# Adafruit_Feather_STM32F405_Express.net
KiCad netlist of a schematic drawn in EAGLE
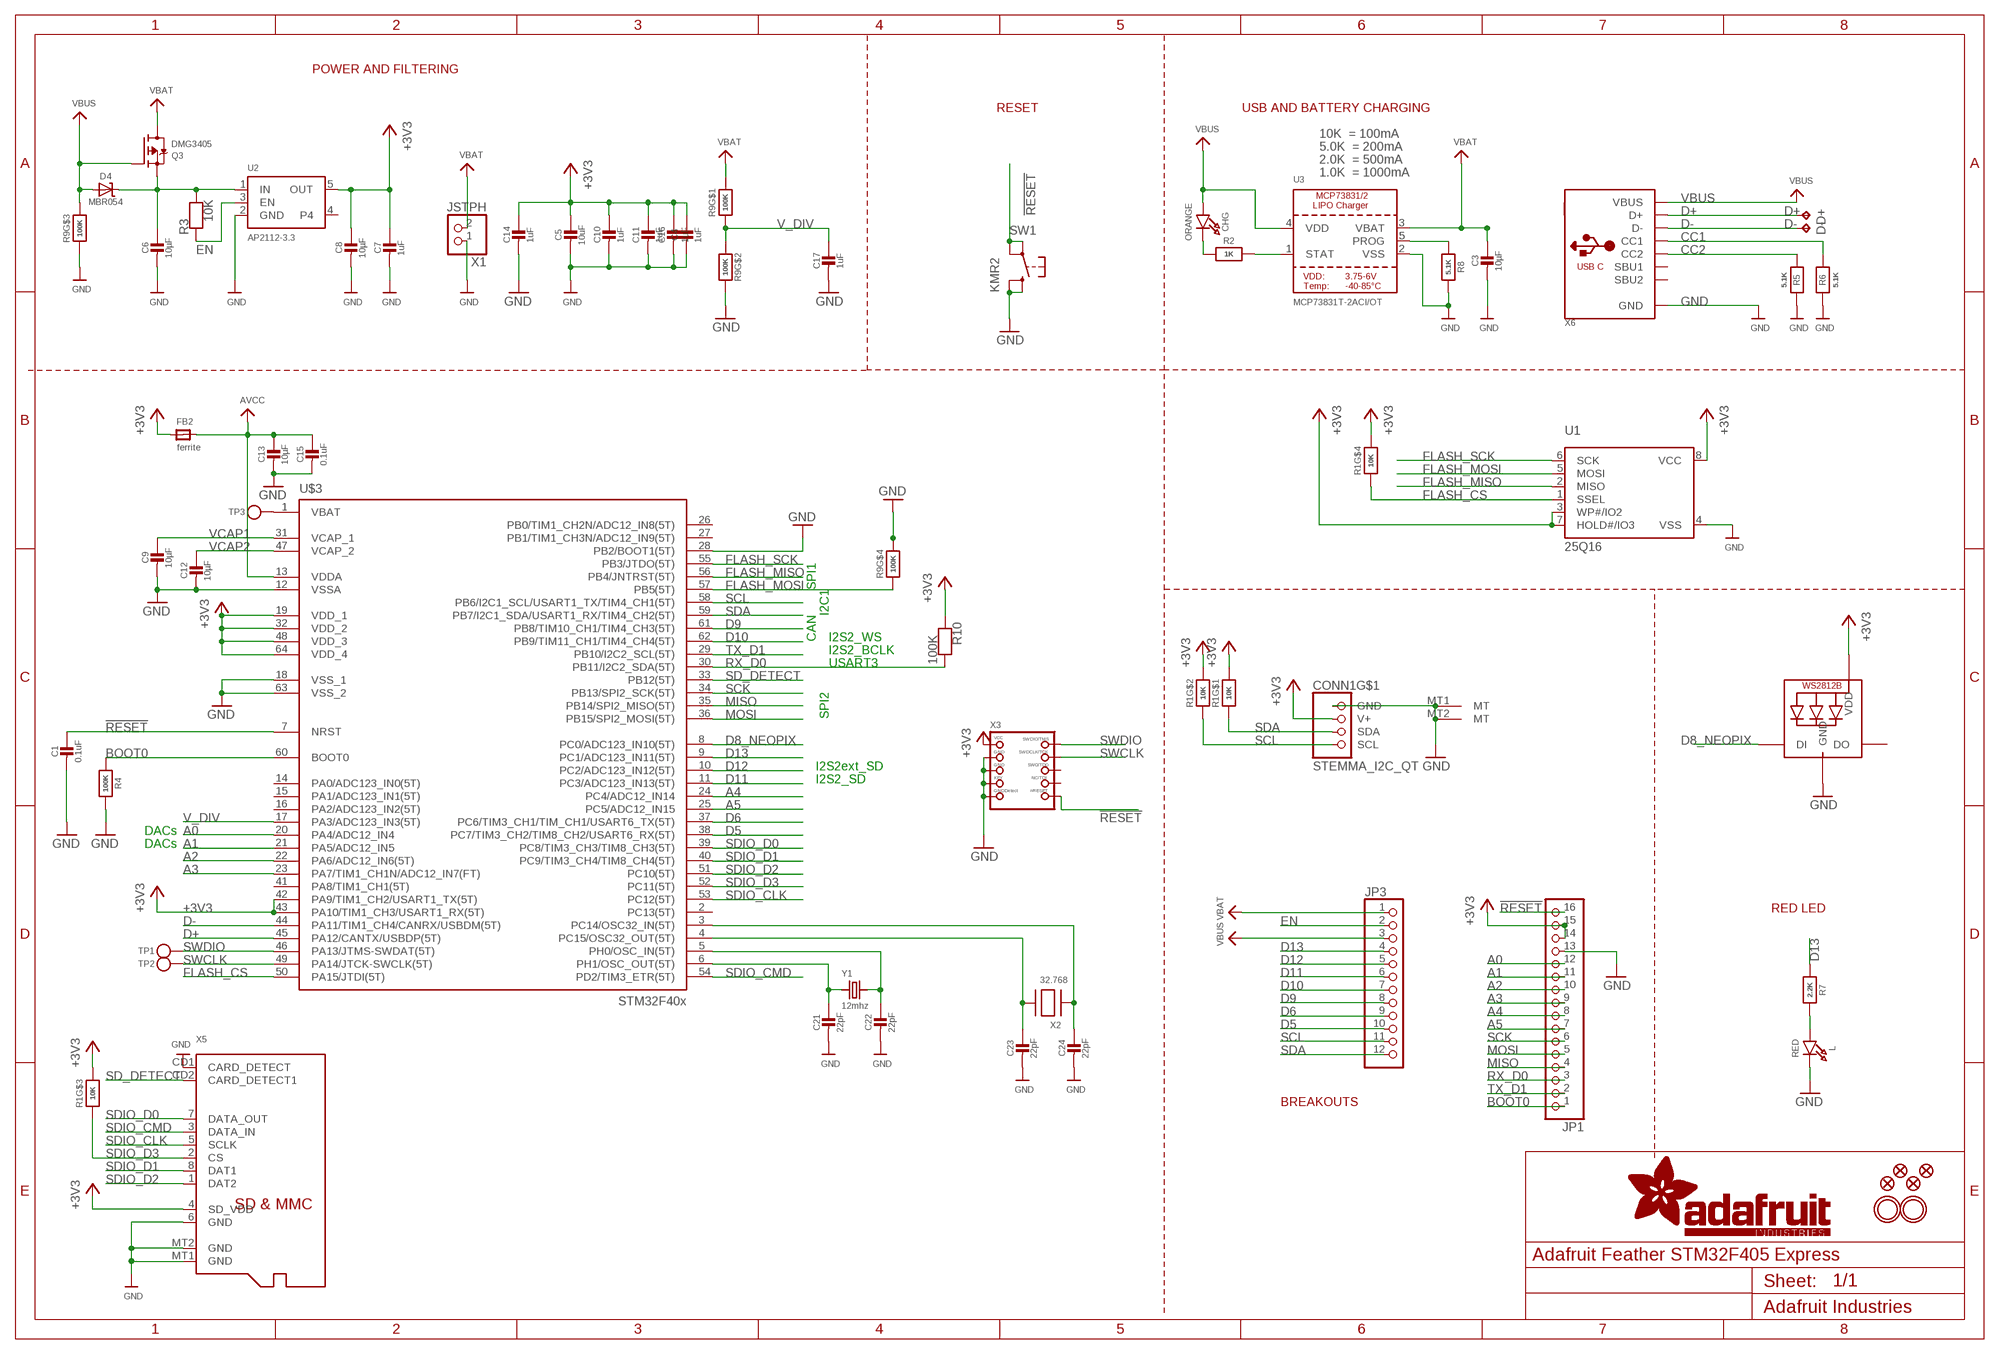
[diagram p0: schematic, sheet 1]

(export (version "E")
  (design (tool "Eeschema 10.0.6"))
  (components
    (comp (ref "C1")
      (value "0.1uF")
      (footprint "eagle-import:0603-NO")
      (libsource (lib "eagle-import") (part "CAP_CERAMIC0603_NO"))
    )
    (comp (ref "C2")
      (value "22pF")
      (footprint "eagle-import:RESPACK_4X0603")
      (libsource (lib "eagle-import") (part "CAP_4PACK1206"))
    )
    (comp (ref "C3")
      (value "10µF")
      (footprint "eagle-import:0805-NO")
      (libsource (lib "eagle-import") (part "CAP_CERAMIC0805-NOOUTLINE"))
    )
    (comp (ref "C4")
      (value "1uF")
      (footprint "eagle-import:0603-NO")
      (libsource (lib "eagle-import") (part "CAP_CERAMIC0603_NO"))
    )
    (comp (ref "C5")
      (value "10uF")
      (footprint "eagle-import:0805-NO")
      (libsource (lib "eagle-import") (part "CAP_CERAMIC0805-NOOUTLINE"))
    )
    (comp (ref "C6")
      (value "10µF")
      (footprint "eagle-import:0805-NO")
      (libsource (lib "eagle-import") (part "CAP_CERAMIC0805-NOOUTLINE"))
    )
    (comp (ref "C7")
      (value "1uF")
      (footprint "eagle-import:0603-NO")
      (libsource (lib "eagle-import") (part "CAP_CERAMIC0603_NO"))
    )
    (comp (ref "C8")
      (value "10µF")
      (footprint "eagle-import:0805-NO")
      (fields (field (name "REV") "B"))
      (libsource (lib "eagle-import") (part "CAP_CERAMIC0805-NOOUTLINE"))
    )
    (comp (ref "C9")
      (value "10µF")
      (footprint "eagle-import:0805-NO")
      (libsource (lib "eagle-import") (part "CAP_CERAMIC0805-NOOUTLINE"))
    )
    (comp (ref "C10")
      (value "1uF")
      (footprint "eagle-import:0603-NO")
      (libsource (lib "eagle-import") (part "CAP_CERAMIC0603_NO"))
    )
    (comp (ref "C11")
      (value "1uF")
      (footprint "eagle-import:0603-NO")
      (libsource (lib "eagle-import") (part "CAP_CERAMIC0603_NO"))
    )
    (comp (ref "C12")
      (value "10µF")
      (footprint "eagle-import:0805-NO")
      (libsource (lib "eagle-import") (part "CAP_CERAMIC0805-NOOUTLINE"))
    )
    (comp (ref "C13")
      (value "10µF")
      (footprint "eagle-import:0805-NO")
      (libsource (lib "eagle-import") (part "CAP_CERAMIC0805-NOOUTLINE"))
    )
    (comp (ref "C14")
      (value "1uF")
      (footprint "eagle-import:0603-NO")
      (libsource (lib "eagle-import") (part "CAP_CERAMIC0603_NO"))
    )
    (comp (ref "C15")
      (value "0.1uF")
      (footprint "eagle-import:0603-NO")
      (libsource (lib "eagle-import") (part "CAP_CERAMIC0603_NO"))
    )
    (comp (ref "C16")
      (value "1uF")
      (footprint "eagle-import:0603-NO")
      (libsource (lib "eagle-import") (part "CAP_CERAMIC0603_NO"))
    )
    (comp (ref "C17")
      (value "1uF")
      (footprint "eagle-import:0603-NO")
      (libsource (lib "eagle-import") (part "CAP_CERAMIC0603_NO"))
    )
    (comp (ref "CHG")
      (value "ORANGE")
      (footprint "eagle-import:CHIPLED_0805_NOOUTLINE")
      (libsource (lib "eagle-import") (part "LED0805_NOOUTLINE"))
    )
    (comp (ref "CONN1")
      (value "STEMMA_I2C_QT")
      (footprint "eagle-import:JST_SH4")
      (libsource (lib "eagle-import") (part "STEMMA_I2C_QT"))
    )
    (comp (ref "D+")
      (value "TPB1,27")
      (footprint "eagle-import:B1,27")
      (libsource (lib "eagle-import") (part "TPB1,27"))
    )
    (comp (ref "D-")
      (value "TPB1,27")
      (footprint "eagle-import:B1,27")
      (libsource (lib "eagle-import") (part "TPB1,27"))
    )
    (comp (ref "D4")
      (value "MBR054")
      (footprint "eagle-import:SOD-123")
      (libsource (lib "eagle-import") (part "DIODE-SCHOTTKYSOD-123"))
    )
    (comp (ref "FB2")
      (value "ferrite")
      (footprint "eagle-import:0805-NO")
      (libsource (lib "eagle-import") (part "FERRITE-0805NO"))
    )
    (comp (ref "JP1")
      (value "HEADER-1X16ROUND")
      (footprint "eagle-import:1X16_ROUND")
      (libsource (lib "eagle-import") (part "HEADER-1X16ROUND"))
    )
    (comp (ref "JP3")
      (value "HEADER-1X12")
      (footprint "eagle-import:1X12_ROUND")
      (libsource (lib "eagle-import") (part "HEADER-1X12"))
    )
    (comp (ref "L")
      (value "RED")
      (footprint "eagle-import:CHIPLED_0805_NOOUTLINE")
      (libsource (lib "eagle-import") (part "LED0805_NOOUTLINE"))
    )
    (comp (ref "LED1")
      (value "WS2812B3535")
      (footprint "eagle-import:LED3535")
      (libsource (lib "eagle-import") (part "WS2812B3535"))
    )
    (comp (ref "Q3")
      (value "DMG3405")
      (footprint "eagle-import:SOT23-R")
      (libsource (lib "eagle-import") (part "MOSFET-P"))
    )
    (comp (ref "R1")
      (value "10K")
      (footprint "eagle-import:RESPACK_4X0603_NO")
      (libsource (lib "eagle-import") (part "RESISTOR_4PACK_NO"))
    )
    (comp (ref "R2")
      (value "1K")
      (footprint "eagle-import:0603-NO")
      (libsource (lib "eagle-import") (part "RESISTOR_0603_NOOUT"))
    )
    (comp (ref "R3")
      (value "10K")
      (footprint "eagle-import:0603-NO")
      (libsource (lib "eagle-import") (part "RESISTOR_0603_NOOUT"))
    )
    (comp (ref "R4")
      (value "100K")
      (footprint "eagle-import:0603-NO")
      (libsource (lib "eagle-import") (part "RESISTOR_0603_NOOUT"))
    )
    (comp (ref "R5")
      (value "5.1K")
      (footprint "eagle-import:0603-NO")
      (libsource (lib "eagle-import") (part "RESISTOR_0603_NOOUT"))
    )
    (comp (ref "R6")
      (value "5.1K")
      (footprint "eagle-import:0603-NO")
      (libsource (lib "eagle-import") (part "RESISTOR_0603_NOOUT"))
    )
    (comp (ref "R7")
      (value "2.2K")
      (footprint "eagle-import:0603-NO")
      (libsource (lib "eagle-import") (part "RESISTOR_0603_NOOUT"))
    )
    (comp (ref "R8")
      (value "5.1K")
      (footprint "eagle-import:0603-NO")
      (libsource (lib "eagle-import") (part "RESISTOR_0603_NOOUT"))
    )
    (comp (ref "R9")
      (value "100K")
      (footprint "eagle-import:RESPACK_4X0603_NO")
      (libsource (lib "eagle-import") (part "RESISTOR_4PACK_NO"))
    )
    (comp (ref "R10")
      (value "100K")
      (footprint "eagle-import:0603-NO")
      (libsource (lib "eagle-import") (part "RESISTOR_0603_NOOUT"))
    )
    (comp (ref "SW1")
      (value "KMR2")
      (footprint "eagle-import:BTN_KMR2_4.6X2.8")
      (libsource (lib "eagle-import") (part "SWITCH_TACT_SMT4.6X2.8"))
    )
    (comp (ref "TP1")
      (value "TESTPOINTROUND1.5MM")
      (footprint "eagle-import:TESTPOINT_ROUND_1.5MM")
      (libsource (lib "eagle-import") (part "TESTPOINTROUND1.5MM"))
    )
    (comp (ref "TP2")
      (value "TESTPOINTROUND1.5MM")
      (footprint "eagle-import:TESTPOINT_ROUND_1.5MM")
      (libsource (lib "eagle-import") (part "TESTPOINTROUND1.5MM"))
    )
    (comp (ref "TP3")
      (value "TESTPOINTROUND1.5MM")
      (footprint "eagle-import:TESTPOINT_ROUND_1.5MM")
      (libsource (lib "eagle-import") (part "TESTPOINTROUND1.5MM"))
    )
    (comp (ref "U$3")
      (value "STM32F405R")
      (footprint "eagle-import:TQFP64")
      (libsource (lib "eagle-import") (part "STM32F405R"))
    )
    (comp (ref "U$5")
      (value "FIDUCIAL_1MM")
      (footprint "eagle-import:FIDUCIAL_1MM")
      (libsource (lib "eagle-import") (part "FIDUCIAL_1MM"))
    )
    (comp (ref "U$31")
      (value "MOUNTINGHOLE2.5")
      (footprint "eagle-import:MOUNTINGHOLE_2.5_PLATED")
      (libsource (lib "eagle-import") (part "MOUNTINGHOLE2.5"))
    )
    (comp (ref "U$32")
      (value "MOUNTINGHOLE2.5")
      (footprint "eagle-import:MOUNTINGHOLE_2.5_PLATED")
      (libsource (lib "eagle-import") (part "MOUNTINGHOLE2.5"))
    )
    (comp (ref "U$34")
      (value "FIDUCIAL_1MM")
      (footprint "eagle-import:FIDUCIAL_1MM")
      (libsource (lib "eagle-import") (part "FIDUCIAL_1MM"))
    )
    (comp (ref "U$35")
      (value "FIDUCIAL_1MM")
      (footprint "eagle-import:FIDUCIAL_1MM")
      (libsource (lib "eagle-import") (part "FIDUCIAL_1MM"))
    )
    (comp (ref "U$37")
      (value "FIDUCIAL_1MM")
      (footprint "eagle-import:FIDUCIAL_1MM")
      (libsource (lib "eagle-import") (part "FIDUCIAL_1MM"))
    )
    (comp (ref "U1")
      (value "25Q16")
      (footprint "eagle-import:SOIC8_150MIL")
      (libsource (lib "eagle-import") (part "SPIFLASH_8PIN"))
    )
    (comp (ref "U2")
      (value "AP2112-3.3")
      (footprint "eagle-import:SOT23-5")
      (libsource (lib "eagle-import") (part "VREG_SOT23-5"))
    )
    (comp (ref "U3")
      (value "MCP73831T-2ACI/OT")
      (footprint "eagle-import:SOT23-5")
      (libsource (lib "eagle-import") (part "MCP73831/2"))
    )
    (comp (ref "X1")
      (value "JSTPH")
      (footprint "eagle-import:JSTPH2")
      (libsource (lib "eagle-import") (part "CON_JST_PH_2PIN"))
    )
    (comp (ref "X2")
      (value "32.768")
      (footprint "eagle-import:XTAL3215")
      (libsource (lib "eagle-import") (part "XTAL-3.2X1.5"))
    )
    (comp (ref "X3")
      (value "JTAG-CORTEX")
      (footprint "eagle-import:2X05_1.27MM_SMT")
      (libsource (lib "eagle-import") (part "JTAG-CORTEX"))
    )
    (comp (ref "X5")
      (value "MICROSD")
      (footprint "eagle-import:MICROSD")
      (libsource (lib "eagle-import") (part "MICROSD"))
    )
    (comp (ref "X6")
      (value "USB_C")
      (footprint "eagle-import:USB_C_CUSB31-CFM2AX-01-X")
      (libsource (lib "eagle-import") (part "USB_C"))
    )
    (comp (ref "Y1")
      (value "12mhz")
      (footprint "eagle-import:CRYSTAL_2.5X2")
      (libsource (lib "eagle-import") (part "CRYSTAL2.5X2.0"))
    )
  )
  (nets
    (net (code "1") (name "+3V3") (class "Default")
      (node (ref "C10") (pin "1") (pinfunction "1_1") (pintype "passive"))
      (node (ref "C11") (pin "1") (pinfunction "1_1") (pintype "passive"))
      (node (ref "C14") (pin "1") (pinfunction "1_1") (pintype "passive"))
      (node (ref "C16") (pin "1") (pinfunction "1_1") (pintype "passive"))
      (node (ref "C4") (pin "1") (pinfunction "1_1") (pintype "passive"))
      (node (ref "C5") (pin "1") (pinfunction "1_1") (pintype "passive"))
      (node (ref "C7") (pin "1") (pinfunction "1_1") (pintype "passive"))
      (node (ref "C8") (pin "1") (pinfunction "1_1") (pintype "passive"))
      (node (ref "CONN1") (pin "2") (pinfunction "V+_2") (pintype "passive"))
      (node (ref "FB2") (pin "1") (pinfunction "P$1_1") (pintype "passive"))
      (node (ref "JP1") (pin "14") (pinfunction "14_14") (pintype "passive"))
      (node (ref "JP1") (pin "15") (pinfunction "15_15") (pintype "passive"))
      (node (ref "LED1") (pin "2") (pinfunction "VDD_2") (pintype "power_in"))
      (node (ref "R1") (pin "5") (pinfunction "2_5") (pintype "passive"))
      (node (ref "R1") (pin "6") (pinfunction "2_6") (pintype "passive"))
      (node (ref "R1") (pin "7") (pinfunction "2_7") (pintype "passive"))
      (node (ref "R1") (pin "8") (pinfunction "2_8") (pintype "passive"))
      (node (ref "R10") (pin "1") (pinfunction "1_1") (pintype "passive"))
      (node (ref "U$3") (pin "19") (pinfunction "VDD_1_19") (pintype "bidirectional"))
      (node (ref "U$3") (pin "32") (pinfunction "VDD_2_32") (pintype "bidirectional"))
      (node (ref "U$3") (pin "42") (pinfunction "PA9/TIM1_CH2/USART1_TX(5T)_42") (pintype "bidirectional"))
      (node (ref "U$3") (pin "43") (pinfunction "PA10/TIM1_CH3/USART1_RX(5T)_43") (pintype "bidirectional"))
      (node (ref "U$3") (pin "48") (pinfunction "VDD_3_48") (pintype "bidirectional"))
      (node (ref "U$3") (pin "64") (pinfunction "VDD_4_64") (pintype "bidirectional"))
      (node (ref "U1") (pin "3") (pinfunction "WP#/IO2_3") (pintype "bidirectional"))
      (node (ref "U1") (pin "7") (pinfunction "HOLD#/IO3_7") (pintype "bidirectional"))
      (node (ref "U1") (pin "8") (pinfunction "VCC_8") (pintype "bidirectional"))
      (node (ref "U2") (pin "5") (pinfunction "OUT_5") (pintype "power_in"))
      (node (ref "X3") (pin "1") (pinfunction "VCC_1") (pintype "power_in"))
      (node (ref "X5") (pin "4") (pinfunction "SD_VDD_4") (pintype "power_in"))
    )
    (net (code "2") (name "/A0") (class "Default")
      (node (ref "JP1") (pin "12") (pinfunction "12_12") (pintype "passive"))
      (node (ref "U$3") (pin "20") (pinfunction "PA4/ADC12_IN4_20") (pintype "bidirectional"))
    )
    (net (code "3") (name "/A1") (class "Default")
      (node (ref "JP1") (pin "11") (pinfunction "11_11") (pintype "passive"))
      (node (ref "U$3") (pin "21") (pinfunction "PA5/ADC12_IN5_21") (pintype "bidirectional"))
    )
    (net (code "4") (name "/A2") (class "Default")
      (node (ref "JP1") (pin "10") (pinfunction "10_10") (pintype "passive"))
      (node (ref "U$3") (pin "22") (pinfunction "PA6/ADC12_IN6(5T)_22") (pintype "bidirectional"))
    )
    (net (code "5") (name "/A3") (class "Default")
      (node (ref "JP1") (pin "9") (pinfunction "9_9") (pintype "passive"))
      (node (ref "U$3") (pin "23") (pinfunction "PA7/TIM1_CH1N/ADC12_IN7(FT)_23") (pintype "bidirectional"))
    )
    (net (code "6") (name "/A4") (class "Default")
      (node (ref "JP1") (pin "8") (pinfunction "8_8") (pintype "passive"))
      (node (ref "U$3") (pin "24") (pinfunction "PC4/ADC12_IN14_24") (pintype "bidirectional"))
    )
    (net (code "7") (name "/A5") (class "Default")
      (node (ref "JP1") (pin "7") (pinfunction "7_7") (pintype "passive"))
      (node (ref "U$3") (pin "25") (pinfunction "PC5/ADC12_IN15_25") (pintype "bidirectional"))
    )
    (net (code "8") (name "/BOOT0") (class "Default")
      (node (ref "JP1") (pin "1") (pinfunction "1_1") (pintype "passive"))
      (node (ref "R4") (pin "1") (pinfunction "1_1") (pintype "passive"))
      (node (ref "U$3") (pin "60") (pinfunction "BOOT0_60") (pintype "bidirectional"))
    )
    (net (code "9") (name "/CC1") (class "Default")
      (node (ref "R6") (pin "2") (pinfunction "2_2") (pintype "passive"))
      (node (ref "X6") (pin "A5") (pinfunction "CC1_A5") (pintype "bidirectional"))
    )
    (net (code "10") (name "/CC2") (class "Default")
      (node (ref "R5") (pin "2") (pinfunction "2_2") (pintype "passive"))
      (node (ref "X6") (pin "B5") (pinfunction "CC2_B5") (pintype "bidirectional"))
    )
    (net (code "11") (name "/D+") (class "Default")
      (node (ref "D+") (pin "TP") (pinfunction "TP_TP") (pintype "input"))
      (node (ref "U$3") (pin "45") (pinfunction "PA12/CANTX/USBDP(5T)_45") (pintype "bidirectional"))
      (node (ref "X6") (pin "A6") (pinfunction "D+_A6") (pintype "bidirectional"))
      (node (ref "X6") (pin "B6") (pinfunction "D+_B6") (pintype "bidirectional"))
    )
    (net (code "12") (name "/D-") (class "Default")
      (node (ref "D-") (pin "TP") (pinfunction "TP_TP") (pintype "input"))
      (node (ref "U$3") (pin "44") (pinfunction "PA11/TIM1_CH4/CANRX/USBDM(5T)_44") (pintype "bidirectional"))
      (node (ref "X6") (pin "A7") (pinfunction "D-_A7") (pintype "bidirectional"))
      (node (ref "X6") (pin "B7") (pinfunction "D-_B7") (pintype "bidirectional"))
    )
    (net (code "13") (name "/D5") (class "Default")
      (node (ref "JP3") (pin "10") (pinfunction "10_10") (pintype "passive"))
      (node (ref "U$3") (pin "38") (pinfunction "PC7/TIM3_CH2/TIM8_CH2/USART6_RX(5T)_38") (pintype "bidirectional"))
    )
    (net (code "14") (name "/D6") (class "Default")
      (node (ref "JP3") (pin "9") (pinfunction "9_9") (pintype "passive"))
      (node (ref "U$3") (pin "37") (pinfunction "PC6/TIM3_CH1/TIM_CH1/USART6_TX(5T)_37") (pintype "bidirectional"))
    )
    (net (code "15") (name "/D8_NEOPIX") (class "Default")
      (node (ref "LED1") (pin "1") (pinfunction "DI_1") (pintype "input"))
      (node (ref "U$3") (pin "8") (pinfunction "PC0/ADC123_IN10(5T)_8") (pintype "bidirectional"))
    )
    (net (code "16") (name "/D9") (class "Default")
      (node (ref "JP3") (pin "8") (pinfunction "8_8") (pintype "passive"))
      (node (ref "U$3") (pin "61") (pinfunction "PB8/TIM10_CH1/TIM4_CH3(5T)_61") (pintype "bidirectional"))
    )
    (net (code "17") (name "/D10") (class "Default")
      (node (ref "JP3") (pin "7") (pinfunction "7_7") (pintype "passive"))
      (node (ref "U$3") (pin "62") (pinfunction "PB9/TIM11_CH1/TIM4_CH4(5T)_62") (pintype "bidirectional"))
    )
    (net (code "18") (name "/D11") (class "Default")
      (node (ref "JP3") (pin "6") (pinfunction "6_6") (pintype "passive"))
      (node (ref "U$3") (pin "11") (pinfunction "PC3/ADC123_IN13(5T)_11") (pintype "bidirectional"))
    )
    (net (code "19") (name "/D12") (class "Default")
      (node (ref "JP3") (pin "5") (pinfunction "5_5") (pintype "passive"))
      (node (ref "U$3") (pin "10") (pinfunction "PC2/ADC123_IN12(5T)_10") (pintype "bidirectional"))
    )
    (net (code "20") (name "/D13") (class "Default")
      (node (ref "JP3") (pin "4") (pinfunction "4_4") (pintype "passive"))
      (node (ref "R7") (pin "1") (pinfunction "1_1") (pintype "passive"))
      (node (ref "U$3") (pin "9") (pinfunction "PC1/ADC123_IN11(5T)_9") (pintype "bidirectional"))
    )
    (net (code "21") (name "/EN") (class "Default")
      (node (ref "JP3") (pin "2") (pinfunction "2_2") (pintype "passive"))
      (node (ref "R3") (pin "1") (pinfunction "1_1") (pintype "passive"))
      (node (ref "U2") (pin "3") (pinfunction "EN_3") (pintype "input"))
    )
    (net (code "22") (name "/FLASH_CS") (class "Default")
      (node (ref "R1") (pin "4") (pinfunction "1_4") (pintype "passive"))
      (node (ref "U$3") (pin "50") (pinfunction "PA15/JTDI(5T)_50") (pintype "bidirectional"))
      (node (ref "U1") (pin "1") (pinfunction "SSEL_1") (pintype "bidirectional"))
    )
    (net (code "23") (name "/FLASH_MISO") (class "Default")
      (node (ref "U$3") (pin "56") (pinfunction "PB4/JNTRST(5T)_56") (pintype "bidirectional"))
      (node (ref "U1") (pin "2") (pinfunction "MISO_2") (pintype "bidirectional"))
    )
    (net (code "24") (name "/FLASH_MOSI") (class "Default")
      (node (ref "R9") (pin "4") (pinfunction "1_4") (pintype "passive"))
      (node (ref "U$3") (pin "57") (pinfunction "PB5(5T)_57") (pintype "bidirectional"))
      (node (ref "U1") (pin "5") (pinfunction "MOSI_5") (pintype "bidirectional"))
    )
    (net (code "25") (name "/FLASH_SCK") (class "Default")
      (node (ref "U$3") (pin "55") (pinfunction "PB3/JTDO(5T)_55") (pintype "bidirectional"))
      (node (ref "U1") (pin "6") (pinfunction "SCK_6") (pintype "bidirectional"))
    )
    (net (code "26") (name "/MISO") (class "Default")
      (node (ref "JP1") (pin "4") (pinfunction "4_4") (pintype "passive"))
      (node (ref "U$3") (pin "35") (pinfunction "PB14/SPI2_MISO(5T)_35") (pintype "bidirectional"))
    )
    (net (code "27") (name "/MOSI") (class "Default")
      (node (ref "JP1") (pin "5") (pinfunction "5_5") (pintype "passive"))
      (node (ref "U$3") (pin "36") (pinfunction "PB15/SPI2_MOSI(5T)_36") (pintype "bidirectional"))
    )
    (net (code "28") (name "/RX_D0") (class "Default")
      (node (ref "JP1") (pin "3") (pinfunction "3_3") (pintype "passive"))
      (node (ref "R10") (pin "2") (pinfunction "2_2") (pintype "passive"))
      (node (ref "U$3") (pin "30") (pinfunction "PB11/I2C2_SDA(5T)_30") (pintype "bidirectional"))
    )
    (net (code "29") (name "/SCK") (class "Default")
      (node (ref "JP1") (pin "6") (pinfunction "6_6") (pintype "passive"))
      (node (ref "U$3") (pin "34") (pinfunction "PB13/SPI2_SCK(5T)_34") (pintype "bidirectional"))
    )
    (net (code "30") (name "/SCL") (class "Default")
      (node (ref "CONN1") (pin "4") (pinfunction "SCL_4") (pintype "passive"))
      (node (ref "JP3") (pin "11") (pinfunction "11_11") (pintype "passive"))
      (node (ref "R1") (pin "2") (pinfunction "1_2") (pintype "passive"))
      (node (ref "U$3") (pin "58") (pinfunction "PB6/I2C1_SCL/USART1_TX/TIM4_CH1(5T)_58") (pintype "bidirectional"))
    )
    (net (code "31") (name "/SDA") (class "Default")
      (node (ref "CONN1") (pin "3") (pinfunction "SDA_3") (pintype "passive"))
      (node (ref "JP3") (pin "12") (pinfunction "12_12") (pintype "passive"))
      (node (ref "R1") (pin "1") (pinfunction "1_1") (pintype "passive"))
      (node (ref "U$3") (pin "59") (pinfunction "PB7/I2C1_SDA/USART1_RX/TIM4_CH2(5T)_59") (pintype "bidirectional"))
    )
    (net (code "32") (name "/SDIO_CLK") (class "Default")
      (node (ref "U$3") (pin "53") (pinfunction "PC12(5T)_53") (pintype "bidirectional"))
      (node (ref "X5") (pin "5") (pinfunction "SCLK_5") (pintype "input"))
    )
    (net (code "33") (name "/SDIO_CMD") (class "Default")
      (node (ref "U$3") (pin "54") (pinfunction "PD2/TIM3_ETR(5T)_54") (pintype "bidirectional"))
      (node (ref "X5") (pin "3") (pinfunction "DATA_IN_3") (pintype "input"))
    )
    (net (code "34") (name "/SDIO_D0") (class "Default")
      (node (ref "U$3") (pin "39") (pinfunction "PC8/TIM3_CH3/TIM8_CH3(5T)_39") (pintype "bidirectional"))
      (node (ref "X5") (pin "7") (pinfunction "DATA_OUT_7") (pintype "output"))
    )
    (net (code "35") (name "/SDIO_D1") (class "Default")
      (node (ref "U$3") (pin "40") (pinfunction "PC9/TIM3_CH4/TIM8_CH4(5T)_40") (pintype "bidirectional"))
      (node (ref "X5") (pin "8") (pinfunction "DAT1_8") (pintype "bidirectional"))
    )
    (net (code "36") (name "/SDIO_D2") (class "Default")
      (node (ref "U$3") (pin "51") (pinfunction "PC10(5T)_51") (pintype "bidirectional"))
      (node (ref "X5") (pin "1") (pinfunction "DAT2_1") (pintype "bidirectional"))
    )
    (net (code "37") (name "/SDIO_D3") (class "Default")
      (node (ref "R1") (pin "3") (pinfunction "1_3") (pintype "passive"))
      (node (ref "U$3") (pin "52") (pinfunction "PC11(5T)_52") (pintype "bidirectional"))
      (node (ref "X5") (pin "2") (pinfunction "CS_2") (pintype "input"))
    )
    (net (code "38") (name "/SD_DETECT") (class "Default")
      (node (ref "U$3") (pin "33") (pinfunction "PB12(5T)_33") (pintype "bidirectional"))
      (node (ref "X5") (pin "CD2") (pinfunction "CARD_DETECT1_CD2") (pintype "passive"))
    )
    (net (code "39") (name "/SWCLK") (class "Default")
      (node (ref "TP2") (pin "P$1") (pinfunction "P$1_P$1") (pintype "bidirectional"))
      (node (ref "U$3") (pin "49") (pinfunction "PA14/JTCK-SWCLK(5T)_49") (pintype "bidirectional"))
      (node (ref "X3") (pin "4") (pinfunction "SWDCLK_4") (pintype "bidirectional"))
    )
    (net (code "40") (name "/SWDIO") (class "Default")
      (node (ref "TP1") (pin "P$1") (pinfunction "P$1_P$1") (pintype "bidirectional"))
      (node (ref "U$3") (pin "46") (pinfunction "PA13/JTMS-SWDAT(5T)_46") (pintype "bidirectional"))
      (node (ref "X3") (pin "2") (pinfunction "SWDIO_2") (pintype "bidirectional"))
    )
    (net (code "41") (name "/TX_D1") (class "Default")
      (node (ref "JP1") (pin "2") (pinfunction "2_2") (pintype "passive"))
      (node (ref "U$3") (pin "29") (pinfunction "PB10/I2C2_SCL(5T)_29") (pintype "bidirectional"))
    )
    (net (code "42") (name "/VCAP1") (class "Default")
      (node (ref "C9") (pin "1") (pinfunction "1_1") (pintype "passive"))
      (node (ref "U$3") (pin "31") (pinfunction "VCAP_1_31") (pintype "bidirectional"))
    )
    (net (code "43") (name "/VCAP2") (class "Default")
      (node (ref "C12") (pin "1") (pinfunction "1_1") (pintype "passive"))
      (node (ref "U$3") (pin "47") (pinfunction "VCAP_2_47") (pintype "bidirectional"))
    )
    (net (code "44") (name "/V_DIV") (class "Default")
      (node (ref "C17") (pin "1") (pinfunction "1_1") (pintype "passive"))
      (node (ref "R9") (pin "1") (pinfunction "1_1") (pintype "passive"))
      (node (ref "R9") (pin "2") (pinfunction "1_2") (pintype "passive"))
      (node (ref "U$3") (pin "17") (pinfunction "PA3/ADC123_IN3(5T)_17") (pintype "bidirectional"))
    )
    (net (code "45") (name "/~{RESET}") (class "Default")
      (node (ref "C1") (pin "1") (pinfunction "1_1") (pintype "passive"))
      (node (ref "JP1") (pin "16") (pinfunction "16_16") (pintype "passive"))
      (node (ref "SW1") (pin "A") (pinfunction "P_A") (pintype "passive"))
      (node (ref "SW1") (pin "A'") (pinfunction "P1_A'") (pintype "passive"))
      (node (ref "U$3") (pin "7") (pinfunction "NRST_7") (pintype "bidirectional"))
      (node (ref "X3") (pin "10") (pinfunction "NRESET_10") (pintype "bidirectional"))
    )
    (net (code "46") (name "AVCC") (class "Default")
      (node (ref "C13") (pin "1") (pinfunction "1_1") (pintype "passive"))
      (node (ref "C15") (pin "1") (pinfunction "1_1") (pintype "passive"))
      (node (ref "FB2") (pin "2") (pinfunction "P$2_2") (pintype "passive"))
      (node (ref "U$3") (pin "13") (pinfunction "VDDA_13") (pintype "bidirectional"))
    )
    (net (code "47") (name "GND") (class "Default")
      (node (ref "C1") (pin "2") (pinfunction "2_2") (pintype "passive"))
      (node (ref "C10") (pin "2") (pinfunction "2_2") (pintype "passive"))
      (node (ref "C11") (pin "2") (pinfunction "2_2") (pintype "passive"))
      (node (ref "C12") (pin "2") (pinfunction "2_2") (pintype "passive"))
      (node (ref "C13") (pin "2") (pinfunction "2_2") (pintype "passive"))
      (node (ref "C14") (pin "2") (pinfunction "2_2") (pintype "passive"))
      (node (ref "C15") (pin "2") (pinfunction "2_2") (pintype "passive"))
      (node (ref "C16") (pin "2") (pinfunction "2_2") (pintype "passive"))
      (node (ref "C17") (pin "2") (pinfunction "2_2") (pintype "passive"))
      (node (ref "C2") (pin "5") (pinfunction "2_5") (pintype "passive"))
      (node (ref "C2") (pin "6") (pinfunction "2_6") (pintype "passive"))
      (node (ref "C2") (pin "7") (pinfunction "2_7") (pintype "passive"))
      (node (ref "C2") (pin "8") (pinfunction "2_8") (pintype "passive"))
      (node (ref "C3") (pin "2") (pinfunction "2_2") (pintype "passive"))
      (node (ref "C4") (pin "2") (pinfunction "2_2") (pintype "passive"))
      (node (ref "C5") (pin "2") (pinfunction "2_2") (pintype "passive"))
      (node (ref "C6") (pin "2") (pinfunction "2_2") (pintype "passive"))
      (node (ref "C7") (pin "2") (pinfunction "2_2") (pintype "passive"))
      (node (ref "C8") (pin "2") (pinfunction "2_2") (pintype "passive"))
      (node (ref "C9") (pin "2") (pinfunction "2_2") (pintype "passive"))
      (node (ref "CONN1") (pin "1") (pinfunction "GND_1") (pintype "passive"))
      (node (ref "CONN1") (pin "MT1") (pinfunction "MT_MT1") (pintype "bidirectional"))
      (node (ref "CONN1") (pin "MT2") (pinfunction "MT_MT2") (pintype "bidirectional"))
      (node (ref "JP1") (pin "13") (pinfunction "13_13") (pintype "passive"))
      (node (ref "L") (pin "C") (pinfunction "C_C") (pintype "passive"))
      (node (ref "LED1") (pin "4") (pinfunction "GND_4") (pintype "power_in"))
      (node (ref "R4") (pin "2") (pinfunction "2_2") (pintype "passive"))
      (node (ref "R5") (pin "1") (pinfunction "1_1") (pintype "passive"))
      (node (ref "R6") (pin "1") (pinfunction "1_1") (pintype "passive"))
      (node (ref "R8") (pin "2") (pinfunction "2_2") (pintype "passive"))
      (node (ref "R9") (pin "3") (pinfunction "1_3") (pintype "passive"))
      (node (ref "R9") (pin "5") (pinfunction "2_5") (pintype "passive"))
      (node (ref "R9") (pin "7") (pinfunction "2_7") (pintype "passive"))
      (node (ref "SW1") (pin "B") (pinfunction "S_B") (pintype "passive"))
      (node (ref "SW1") (pin "B'") (pinfunction "S1_B'") (pintype "passive"))
      (node (ref "U$3") (pin "12") (pinfunction "VSSA_12") (pintype "bidirectional"))
      (node (ref "U$3") (pin "18") (pinfunction "VSS_1_18") (pintype "bidirectional"))
      (node (ref "U$3") (pin "28") (pinfunction "PB2/BOOT1(5T)_28") (pintype "bidirectional"))
      (node (ref "U$3") (pin "63") (pinfunction "VSS_2_63") (pintype "bidirectional"))
      (node (ref "U1") (pin "4") (pinfunction "VSS_4") (pintype "bidirectional"))
      (node (ref "U2") (pin "2") (pinfunction "GND_2") (pintype "power_in"))
      (node (ref "U3") (pin "2") (pinfunction "VSS_2") (pintype "power_in"))
      (node (ref "X1") (pin "1") (pinfunction "1_1") (pintype "passive"))
      (node (ref "X3") (pin "3") (pinfunction "GND_3") (pintype "power_in"))
      (node (ref "X3") (pin "5") (pinfunction "GND_5") (pintype "power_in"))
      (node (ref "X3") (pin "7") (pinfunction "KEY_7") (pintype "bidirectional"))
      (node (ref "X3") (pin "9") (pinfunction "GNDDETECT_9") (pintype "bidirectional"))
      (node (ref "X5") (pin "6") (pinfunction "GND_6") (pintype "power_in"))
      (node (ref "X5") (pin "CD1") (pinfunction "CARD_DETECT_CD1") (pintype "passive"))
      (node (ref "X5") (pin "MT1") (pinfunction "GND_MT1") (pintype "power_in"))
      (node (ref "X5") (pin "MT2") (pinfunction "GND_MT2") (pintype "power_in"))
      (node (ref "X6") (pin "A1B12") (pinfunction "GND_A1B12") (pintype "power_in"))
      (node (ref "X6") (pin "B1A12") (pinfunction "GND_B1A12") (pintype "power_in"))
    )
    (net (code "48") (name "Net-(C2B-1)") (class "Default")
      (node (ref "C2") (pin "2") (pinfunction "1_2") (pintype "passive"))
      (node (ref "U$3") (pin "5") (pinfunction "PH0/OSC_IN(5T)_5") (pintype "bidirectional"))
      (node (ref "Y1") (pin "3") (pinfunction "2_3") (pintype "passive"))
    )
    (net (code "49") (name "Net-(C2C-1)") (class "Default")
      (node (ref "C2") (pin "3") (pinfunction "1_3") (pintype "passive"))
      (node (ref "U$3") (pin "4") (pinfunction "PC15/OSC32_OUT(5T)_4") (pintype "bidirectional"))
      (node (ref "X2") (pin "P$2") (pinfunction "P$2_P$2") (pintype "bidirectional"))
    )
    (net (code "50") (name "Net-(C2D-1)") (class "Default")
      (node (ref "C2") (pin "4") (pinfunction "1_4") (pintype "passive"))
      (node (ref "U$3") (pin "3") (pinfunction "PC14/OSC32_IN(5T)_3") (pintype "bidirectional"))
      (node (ref "X2") (pin "P$1") (pinfunction "P$1_P$1") (pintype "bidirectional"))
    )
    (net (code "51") (name "Net-(CHG-PadC)") (class "Default")
      (node (ref "CHG") (pin "C") (pinfunction "C_C") (pintype "passive"))
      (node (ref "R2") (pin "1") (pinfunction "1_1") (pintype "passive"))
    )
    (net (code "52") (name "Net-(L-PadA)") (class "Default")
      (node (ref "L") (pin "A") (pinfunction "A_A") (pintype "passive"))
      (node (ref "R7") (pin "2") (pinfunction "2_2") (pintype "passive"))
    )
    (net (code "53") (name "Net-(Q3-S)") (class "Default")
      (node (ref "C6") (pin "1") (pinfunction "1_1") (pintype "passive"))
      (node (ref "D4") (pin "C") (pinfunction "C_C") (pintype "passive"))
      (node (ref "Q3") (pin "2") (pinfunction "S_2") (pintype "passive"))
      (node (ref "R3") (pin "2") (pinfunction "2_2") (pintype "passive"))
      (node (ref "U2") (pin "1") (pinfunction "IN_1") (pintype "power_in"))
    )
    (net (code "54") (name "Net-(U$3-PH1{slash}OSC_OUT(5T))") (class "Default")
      (node (ref "C2") (pin "1") (pinfunction "1_1") (pintype "passive"))
      (node (ref "U$3") (pin "6") (pinfunction "PH1/OSC_OUT(5T)_6") (pintype "bidirectional"))
      (node (ref "Y1") (pin "1") (pinfunction "1_1") (pintype "passive"))
    )
    (net (code "55") (name "Net-(U$3-VBAT)") (class "Default")
      (node (ref "TP3") (pin "P$1") (pinfunction "P$1_P$1") (pintype "bidirectional"))
      (node (ref "U$3") (pin "1") (pinfunction "VBAT_1") (pintype "bidirectional"))
    )
    (net (code "56") (name "Net-(U3-PROG)") (class "Default")
      (node (ref "R8") (pin "1") (pinfunction "1_1") (pintype "passive"))
      (node (ref "U3") (pin "5") (pinfunction "PROG_5") (pintype "input"))
    )
    (net (code "57") (name "Net-(U3-STAT)") (class "Default")
      (node (ref "R2") (pin "2") (pinfunction "2_2") (pintype "passive"))
      (node (ref "U3") (pin "1") (pinfunction "STAT_1") (pintype "output"))
    )
    (net (code "58") (name "VBAT") (class "Default")
      (node (ref "C3") (pin "1") (pinfunction "1_1") (pintype "passive"))
      (node (ref "JP3") (pin "1") (pinfunction "1_1") (pintype "passive"))
      (node (ref "Q3") (pin "3") (pinfunction "D_3") (pintype "passive"))
      (node (ref "R9") (pin "8") (pinfunction "2_8") (pintype "passive"))
      (node (ref "U3") (pin "3") (pinfunction "VBAT_3") (pintype "power_in"))
      (node (ref "X1") (pin "2") (pinfunction "2_2") (pintype "passive"))
    )
    (net (code "59") (name "VBUS") (class "Default")
      (node (ref "CHG") (pin "A") (pinfunction "A_A") (pintype "passive"))
      (node (ref "D4") (pin "A") (pinfunction "A_A") (pintype "passive"))
      (node (ref "JP3") (pin "3") (pinfunction "3_3") (pintype "passive"))
      (node (ref "Q3") (pin "1") (pinfunction "G_1") (pintype "passive"))
      (node (ref "R9") (pin "6") (pinfunction "2_6") (pintype "passive"))
      (node (ref "U3") (pin "4") (pinfunction "VDD_4") (pintype "power_in"))
      (node (ref "X6") (pin "A4B9") (pinfunction "VBUS_A4B9") (pintype "power_in"))
      (node (ref "X6") (pin "B4A9") (pinfunction "VBUS_B4A9") (pintype "power_in"))
    )
    (net (code "60") (name "unconnected-(LED1-DO-Pad3)") (class "Default")
      (node (ref "LED1") (pin "3") (pinfunction "DO_3") (pintype "output"))
    )
    (net (code "61") (name "unconnected-(U$3-PA0{slash}ADC123_IN0(5T)-Pad14)") (class "Default")
      (node (ref "U$3") (pin "14") (pinfunction "PA0/ADC123_IN0(5T)_14") (pintype "bidirectional"))
    )
    (net (code "62") (name "unconnected-(U$3-PA1{slash}ADC123_IN1(5T)-Pad15)") (class "Default")
      (node (ref "U$3") (pin "15") (pinfunction "PA1/ADC123_IN1(5T)_15") (pintype "bidirectional"))
    )
    (net (code "63") (name "unconnected-(U$3-PA2{slash}ADC123_IN2(5T)-Pad16)") (class "Default")
      (node (ref "U$3") (pin "16") (pinfunction "PA2/ADC123_IN2(5T)_16") (pintype "bidirectional"))
    )
    (net (code "64") (name "unconnected-(U$3-PA8{slash}TIM1_CH1(5T)-Pad41)") (class "Default")
      (node (ref "U$3") (pin "41") (pinfunction "PA8/TIM1_CH1(5T)_41") (pintype "bidirectional"))
    )
    (net (code "65") (name "unconnected-(U$3-PB0{slash}TIM1_CH2N{slash}ADC12_IN8(5T)-Pad26)") (class "Default")
      (node (ref "U$3") (pin "26") (pinfunction "PB0/TIM1_CH2N/ADC12_IN8(5T)_26") (pintype "bidirectional"))
    )
    (net (code "66") (name "unconnected-(U$3-PB1{slash}TIM1_CH3N{slash}ADC12_IN9(5T)-Pad27)") (class "Default")
      (node (ref "U$3") (pin "27") (pinfunction "PB1/TIM1_CH3N/ADC12_IN9(5T)_27") (pintype "bidirectional"))
    )
    (net (code "67") (name "unconnected-(U$3-PC13(5T)-Pad2)") (class "Default")
      (node (ref "U$3") (pin "2") (pinfunction "PC13(5T)_2") (pintype "bidirectional"))
    )
    (net (code "68") (name "unconnected-(U2-P4-Pad4)") (class "Default")
      (node (ref "U2") (pin "4") (pinfunction "P4_4") (pintype "bidirectional"))
    )
    (net (code "69") (name "unconnected-(X3-SWO-Pad6)") (class "Default")
      (node (ref "X3") (pin "6") (pinfunction "SWO_6") (pintype "bidirectional"))
    )
    (net (code "70") (name "unconnected-(X3-TDI-Pad8)") (class "Default")
      (node (ref "X3") (pin "8") (pinfunction "TDI_8") (pintype "bidirectional"))
    )
    (net (code "71") (name "unconnected-(X6-SBU1-PadA8)") (class "Default")
      (node (ref "X6") (pin "A8") (pinfunction "SBU1_A8") (pintype "bidirectional"))
    )
    (net (code "72") (name "unconnected-(X6-SBU2-PadB8)") (class "Default")
      (node (ref "X6") (pin "B8") (pinfunction "SBU2_B8") (pintype "bidirectional"))
    )
  )
)
